# RS485.net
KiCad netlist of a schematic drawn in Altium Designer
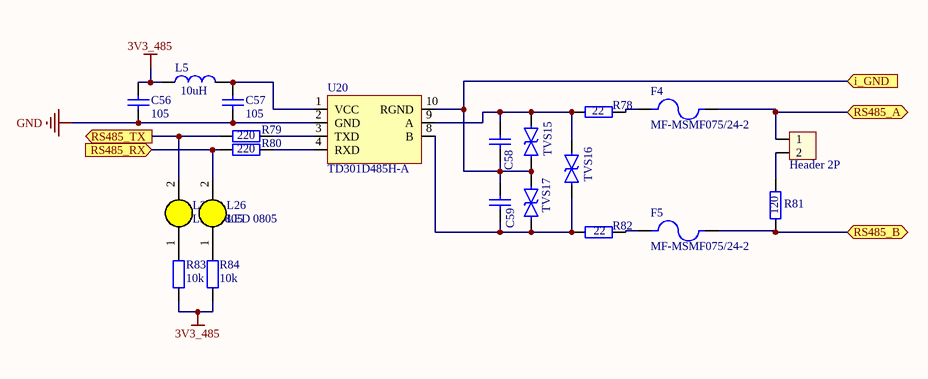
[diagram p0: RS485.SchDoc]

(export (version "E")
  (design (tool "Eeschema 10.0.6"))
  (components
    (comp (ref "C56") (value "105") (footprint "0603_Cap") (libsource (lib "CMN") (part "Ceramic Capacitor")))
    (comp (ref "C57") (value "105") (footprint "0603_Cap") (libsource (lib "CMN") (part "Ceramic Capacitor")))
    (comp (ref "C58") (value "101") (footprint "0603_Cap") (libsource (lib "CMN") (part "Ceramic Capacitor")))
    (comp (ref "C59") (value "101") (footprint "0603_Cap") (libsource (lib "CMN") (part "Ceramic Capacitor")))
    (comp (ref "F4")
      (value "MF-MSMF075/24-2")
      (footprint "FUSER_MF-MSMF075/24-2")
      (description "Polymeric PTC Resettable Fuse 24V 750 mA Ih Surface Mount 1812 (4532 Metric), Concave")
      (fields (field (name "MF") "Bourns"))
      (libsource (lib "MF-MSMF075_24-2") (part "MF-MSMF075/24-2"))
    )
    (comp (ref "F5")
      (value "MF-MSMF075/24-2")
      (footprint "FUSER_MF-MSMF075/24-2")
      (description "Polymeric PTC Resettable Fuse 24V 750 mA Ih Surface Mount 1812 (4532 Metric), Concave")
      (fields (field (name "MF") "Bourns"))
      (libsource (lib "MF-MSMF075_24-2") (part "MF-MSMF075/24-2"))
    )
    (comp (ref "H24")
      (value "Header 2P")
      (footprint "JP 1x2")
      (description "THT")
      (libsource (lib "CMN") (part "Header 2P"))
    )
    (comp (ref "L5")
      (value "10uH")
      (footprint "0603_Inductor")
      (fields (field (name "MP") "B82477G4472M000") (field (name "MF") "EPCOS"))
      (libsource (lib "CMN") (part "Inductor"))
    )
    (comp (ref "L25")
      (value "LED 0805")
      (footprint "LED-0805-Yellow")
      (description "Dán")
      (libsource (lib "Led") (part "LED 0805 Vang"))
    )
    (comp (ref "L26")
      (value "LED 0805")
      (footprint "LED-0805-Yellow")
      (description "Dán")
      (libsource (lib "Led") (part "LED 0805 Vang"))
    )
    (comp (ref "R78") (value "22") (footprint "0603_Res") (libsource (lib "CMN") (part "Resistor")))
    (comp (ref "R79") (value "220") (footprint "0603_Res") (libsource (lib "CMN") (part "Resistor")))
    (comp (ref "R80") (value "220") (footprint "0603_Res") (libsource (lib "CMN") (part "Resistor")))
    (comp (ref "R81") (value "120") (footprint "0603_Res") (libsource (lib "CMN") (part "Resistor")))
    (comp (ref "R82") (value "22") (footprint "0603_Res") (libsource (lib "CMN") (part "Resistor")))
    (comp (ref "R83") (value "10k") (footprint "0603_Res") (libsource (lib "CMN") (part "Resistor")))
    (comp (ref "R84") (value "10k") (footprint "0603_Res") (libsource (lib "CMN") (part "Resistor")))
    (comp (ref "TVS15")
      (value "SMBJ12CA")
      (footprint "SMB - DO-214AA")
      (libsource (lib "CMN") (part "TVS Bi Diode"))
    )
    (comp (ref "TVS16")
      (value "SMBJ12CA")
      (footprint "SMB - DO-214AA")
      (libsource (lib "CMN") (part "TVS Bi Diode"))
    )
    (comp (ref "TVS17")
      (value "SMBJ12CA")
      (footprint "SMB - DO-214AA")
      (libsource (lib "CMN") (part "TVS Bi Diode"))
    )
    (comp (ref "U20")
      (value "TD301D485H-A")
      (footprint "TD301D485H-A")
      (description "TTL to RS485")
      (libsource (lib "CMN") (part "TD301D485H-A"))
    )
  )
  (nets
    (net (code "1") (name "/RS485_A") (class "Default")
      (node (ref "F4") (pin "2") (pinfunction "2_2") (pintype "passive"))
      (node (ref "H24") (pin "1") (pinfunction "1_1") (pintype "passive"))
    )
    (net (code "2") (name "/RS485_B") (class "Default")
      (node (ref "F5") (pin "2") (pinfunction "2_2") (pintype "passive"))
      (node (ref "R81") (pin "2") (pinfunction "2_2") (pintype "passive"))
    )
    (net (code "3") (name "/RS485_RX") (class "Default")
      (node (ref "L26") (pin "2") (pinfunction "K_2") (pintype "passive"))
      (node (ref "R80") (pin "1") (pinfunction "1_1") (pintype "passive"))
    )
    (net (code "4") (name "/RS485_TX") (class "Default")
      (node (ref "L25") (pin "2") (pinfunction "K_2") (pintype "passive"))
      (node (ref "R79") (pin "1") (pinfunction "1_1") (pintype "passive"))
    )
    (net (code "5") (name "/i_GND") (class "Default")
      (node (ref "C58") (pin "2") (pinfunction "2_2") (pintype "passive"))
      (node (ref "C59") (pin "1") (pinfunction "1_1") (pintype "passive"))
      (node (ref "TVS15") (pin "1") (pinfunction "1_1") (pintype "passive"))
      (node (ref "TVS17") (pin "2") (pinfunction "2_2") (pintype "passive"))
      (node (ref "U20") (pin "10") (pinfunction "RGND_10") (pintype "passive"))
    )
    (net (code "6") (name "3V3_485") (class "Default")
      (node (ref "C56") (pin "1") (pinfunction "1_1") (pintype "passive"))
      (node (ref "L5") (pin "1") (pinfunction "1_1") (pintype "passive"))
      (node (ref "R83") (pin "2") (pinfunction "2_2") (pintype "passive"))
      (node (ref "R84") (pin "2") (pinfunction "2_2") (pintype "passive"))
    )
    (net (code "7") (name "GND") (class "Default")
      (node (ref "C56") (pin "2") (pinfunction "2_2") (pintype "passive"))
      (node (ref "C57") (pin "2") (pinfunction "2_2") (pintype "passive"))
      (node (ref "U20") (pin "2") (pinfunction "GND_2") (pintype "passive"))
    )
    (net (code "8") (name "Net-(F4-Pad1)") (class "Default")
      (node (ref "F4") (pin "1") (pinfunction "1_1") (pintype "passive"))
      (node (ref "R78") (pin "1") (pinfunction "1_1") (pintype "passive"))
    )
    (net (code "9") (name "Net-(F5-Pad1)") (class "Default")
      (node (ref "F5") (pin "1") (pinfunction "1_1") (pintype "passive"))
      (node (ref "R82") (pin "1") (pinfunction "1_1") (pintype "passive"))
    )
    (net (code "10") (name "Net-(H24-Pad2)") (class "Default")
      (node (ref "H24") (pin "2") (pinfunction "2_2") (pintype "passive"))
      (node (ref "R81") (pin "1") (pinfunction "1_1") (pintype "passive"))
    )
    (net (code "11") (name "Net-(L25-A)") (class "Default")
      (node (ref "L25") (pin "1") (pinfunction "A_1") (pintype "passive"))
      (node (ref "R83") (pin "1") (pinfunction "1_1") (pintype "passive"))
    )
    (net (code "12") (name "Net-(L26-A)") (class "Default")
      (node (ref "L26") (pin "1") (pinfunction "A_1") (pintype "passive"))
      (node (ref "R84") (pin "1") (pinfunction "1_1") (pintype "passive"))
    )
    (net (code "13") (name "Net-(U20-A)") (class "Default")
      (node (ref "C58") (pin "1") (pinfunction "1_1") (pintype "passive"))
      (node (ref "R78") (pin "2") (pinfunction "2_2") (pintype "passive"))
      (node (ref "TVS15") (pin "2") (pinfunction "2_2") (pintype "passive"))
      (node (ref "TVS16") (pin "2") (pinfunction "2_2") (pintype "passive"))
      (node (ref "U20") (pin "9") (pinfunction "A_9") (pintype "passive"))
    )
    (net (code "14") (name "Net-(U20-B)") (class "Default")
      (node (ref "C59") (pin "2") (pinfunction "2_2") (pintype "passive"))
      (node (ref "R82") (pin "2") (pinfunction "2_2") (pintype "passive"))
      (node (ref "TVS16") (pin "1") (pinfunction "1_1") (pintype "passive"))
      (node (ref "TVS17") (pin "1") (pinfunction "1_1") (pintype "passive"))
      (node (ref "U20") (pin "8") (pinfunction "B_8") (pintype "passive"))
    )
    (net (code "15") (name "Net-(U20-RXD)") (class "Default")
      (node (ref "R80") (pin "2") (pinfunction "2_2") (pintype "passive"))
      (node (ref "U20") (pin "4") (pinfunction "RXD_4") (pintype "passive"))
    )
    (net (code "16") (name "Net-(U20-TXD)") (class "Default")
      (node (ref "R79") (pin "2") (pinfunction "2_2") (pintype "passive"))
      (node (ref "U20") (pin "3") (pinfunction "TXD_3") (pintype "passive"))
    )
    (net (code "17") (name "Net-(U20-VCC)") (class "Default")
      (node (ref "C57") (pin "1") (pinfunction "1_1") (pintype "passive"))
      (node (ref "L5") (pin "2") (pinfunction "2_2") (pintype "passive"))
      (node (ref "U20") (pin "1") (pinfunction "VCC_1") (pintype "passive"))
    )
  )
)
